# MonkeyParty7_1.net
KiCad netlist of a schematic drawn in EAGLE
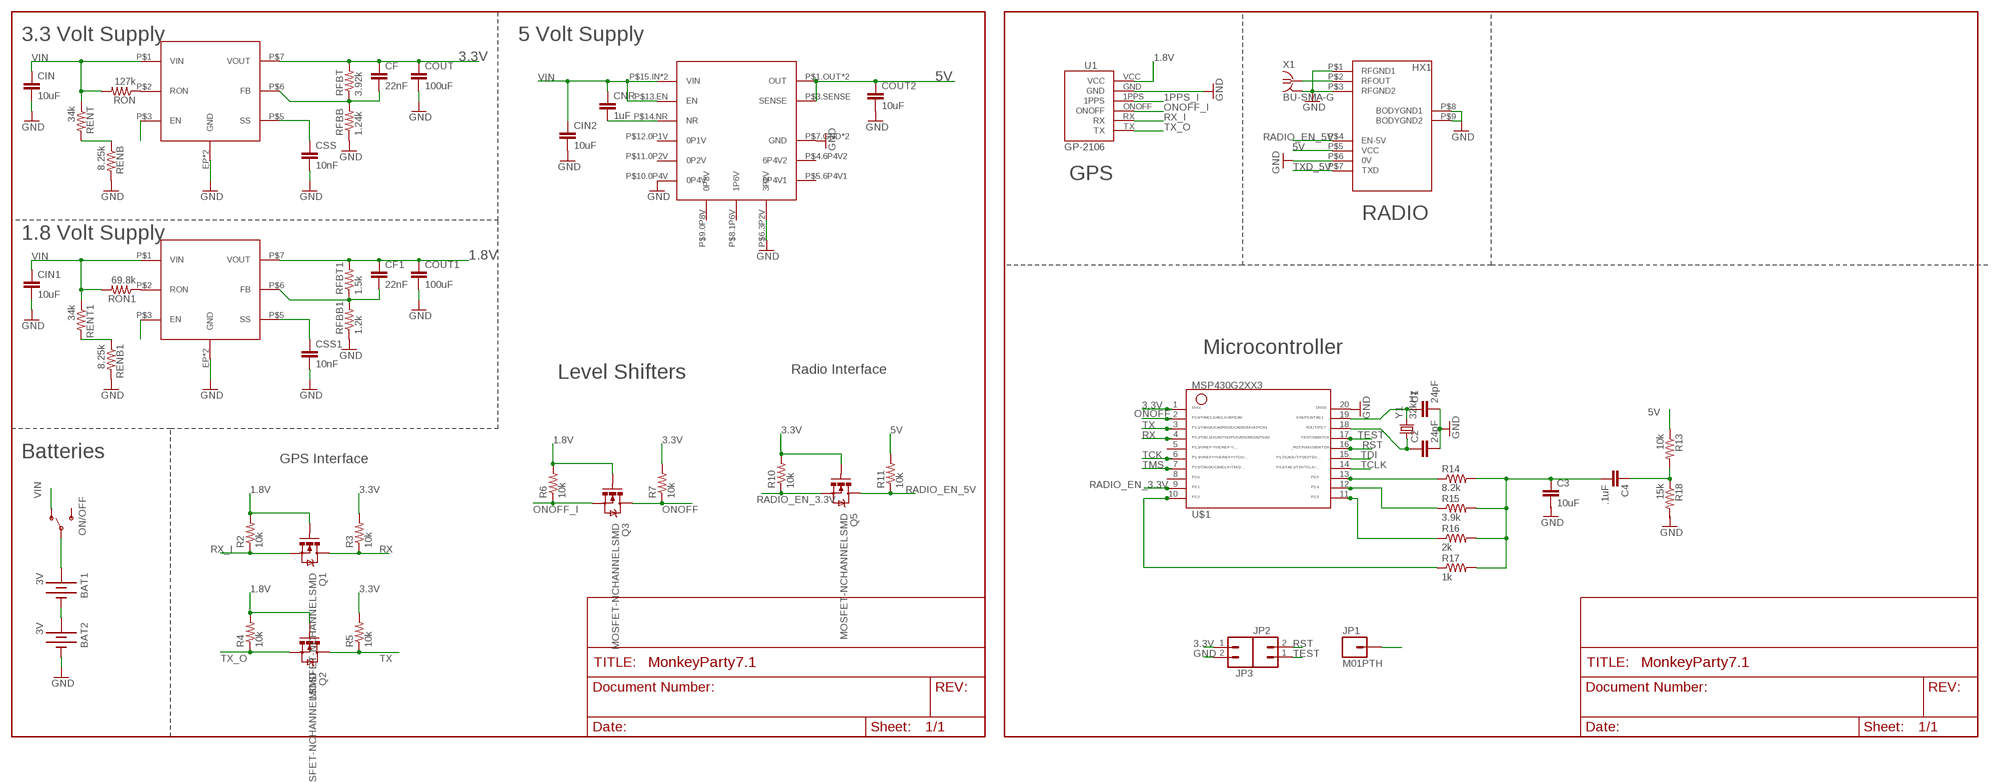
[diagram p0: schematic, sheet 1]

(export (version "E")
  (design (tool "Eeschema 10.0.6"))
  (components
    (comp (ref "1.8VREG")
      (value "LMZ12001")
      (footprint "eagle-import:TO-PMOD7PIN")
      (libsource (lib "eagle-import") (part "LMZ12001"))
    )
    (comp (ref "3.3VREG")
      (value "LMZ12001")
      (footprint "eagle-import:TO-PMOD7PIN")
      (libsource (lib "eagle-import") (part "LMZ12001"))
    )
    (comp (ref "5VREG")
      (value "TPS7A4700")
      (footprint "eagle-import:S-PVQFN-N20")
      (libsource (lib "eagle-import") (part "TPS7A4700"))
    )
    (comp (ref "BAT1")
      (value "3V")
      (footprint "eagle-import:BATTCON_245MM")
      (libsource (lib "eagle-import") (part "BATTERY245MM"))
    )
    (comp (ref "BAT2")
      (value "3V")
      (footprint "eagle-import:BATTCON_245MM")
      (libsource (lib "eagle-import") (part "BATTERY245MM"))
    )
    (comp (ref "C1")
      (value "24pF")
      (footprint "eagle-import:1210")
      (libsource (lib "eagle-import") (part "CAP1210"))
    )
    (comp (ref "C2")
      (value "24pF")
      (footprint "eagle-import:1210")
      (libsource (lib "eagle-import") (part "CAP1210"))
    )
    (comp (ref "C3")
      (value "10uF")
      (footprint "eagle-import:0805")
      (libsource (lib "eagle-import") (part "SparkFun-Capacitors_CAP0805"))
    )
    (comp (ref "C4")
      (value ".1uF")
      (footprint "eagle-import:0805")
      (libsource (lib "eagle-import") (part "SparkFun-Capacitors_CAP0805"))
    )
    (comp (ref "CF")
      (value "22nF")
      (footprint "eagle-import:0805")
      (libsource (lib "eagle-import") (part "CAP0805"))
    )
    (comp (ref "CF1")
      (value "22nF")
      (footprint "eagle-import:0805")
      (libsource (lib "eagle-import") (part "CAP0805"))
    )
    (comp (ref "CIN")
      (value "10uF")
      (footprint "eagle-import:0805")
      (libsource (lib "eagle-import") (part "CAP0805"))
    )
    (comp (ref "CIN1")
      (value "10uF")
      (footprint "eagle-import:0805")
      (libsource (lib "eagle-import") (part "CAP0805"))
    )
    (comp (ref "CIN2")
      (value "10uF")
      (footprint "eagle-import:0805")
      (libsource (lib "eagle-import") (part "CAP0805"))
    )
    (comp (ref "CNR")
      (value "1uF")
      (footprint "eagle-import:0805")
      (libsource (lib "eagle-import") (part "CAP0805"))
    )
    (comp (ref "COUT")
      (value "100uF")
      (footprint "eagle-import:1210")
      (libsource (lib "eagle-import") (part "CAP1210"))
    )
    (comp (ref "COUT1")
      (value "100uF")
      (footprint "eagle-import:1210")
      (libsource (lib "eagle-import") (part "CAP1210"))
    )
    (comp (ref "COUT2")
      (value "10uF")
      (footprint "eagle-import:0805")
      (libsource (lib "eagle-import") (part "CAP0805"))
    )
    (comp (ref "CSS")
      (value "10nF")
      (footprint "eagle-import:1210")
      (libsource (lib "eagle-import") (part "CAP1210"))
    )
    (comp (ref "CSS1")
      (value "10nF")
      (footprint "eagle-import:1210")
      (libsource (lib "eagle-import") (part "CAP1210"))
    )
    (comp (ref "JP1")
      (value "M01PTH")
      (footprint "eagle-import:1X01")
      (libsource (lib "eagle-import") (part "M01PTH"))
    )
    (comp (ref "JP2")
      (value "M02PTH")
      (footprint "eagle-import:1X02")
      (libsource (lib "eagle-import") (part "M02PTH"))
    )
    (comp (ref "JP3")
      (value "M02PTH")
      (footprint "eagle-import:1X02")
      (libsource (lib "eagle-import") (part "M02PTH"))
    )
    (comp (ref "ON/OFF")
      (value "SWITCH-SPSTKIT")
      (footprint "eagle-import:SWITCH-SPDT_KIT")
      (libsource (lib "eagle-import") (part "SWITCH-SPSTKIT"))
    )
    (comp (ref "Q1")
      (value "MOSFET-NCHANNELSMD")
      (footprint "eagle-import:SOT23-3")
      (libsource (lib "eagle-import") (part "MOSFET-NCHANNELSMD"))
    )
    (comp (ref "Q2")
      (value "MOSFET-NCHANNELSMD")
      (footprint "eagle-import:SOT23-3")
      (libsource (lib "eagle-import") (part "MOSFET-NCHANNELSMD"))
    )
    (comp (ref "Q3")
      (value "MOSFET-NCHANNELSMD")
      (footprint "eagle-import:SOT23-3")
      (libsource (lib "eagle-import") (part "MOSFET-NCHANNELSMD"))
    )
    (comp (ref "Q5")
      (value "MOSFET-NCHANNELSMD")
      (footprint "eagle-import:SOT23-3")
      (libsource (lib "eagle-import") (part "MOSFET-NCHANNELSMD"))
    )
    (comp (ref "R2")
      (value "10k")
      (footprint "eagle-import:0805")
      (libsource (lib "eagle-import") (part "RESISTOR0805-RES"))
    )
    (comp (ref "R3")
      (value "10k")
      (footprint "eagle-import:0805")
      (libsource (lib "eagle-import") (part "RESISTOR0805-RES"))
    )
    (comp (ref "R4")
      (value "10k")
      (footprint "eagle-import:0805")
      (libsource (lib "eagle-import") (part "RESISTOR0805-RES"))
    )
    (comp (ref "R5")
      (value "10k")
      (footprint "eagle-import:0805")
      (libsource (lib "eagle-import") (part "RESISTOR0805-RES"))
    )
    (comp (ref "R6")
      (value "10k")
      (footprint "eagle-import:0805")
      (libsource (lib "eagle-import") (part "RESISTOR0805-RES"))
    )
    (comp (ref "R7")
      (value "10k")
      (footprint "eagle-import:0805")
      (libsource (lib "eagle-import") (part "RESISTOR0805-RES"))
    )
    (comp (ref "R10")
      (value "10k")
      (footprint "eagle-import:0805")
      (libsource (lib "eagle-import") (part "RESISTOR0805-RES"))
    )
    (comp (ref "R11")
      (value "10k")
      (footprint "eagle-import:0805")
      (libsource (lib "eagle-import") (part "RESISTOR0805-RES"))
    )
    (comp (ref "R13")
      (value "10k")
      (footprint "eagle-import:0805")
      (libsource (lib "eagle-import") (part "SparkFun-Resistors_RESISTOR0805-RES"))
    )
    (comp (ref "R14")
      (value "8.2k")
      (footprint "eagle-import:0805")
      (libsource (lib "eagle-import") (part "RESISTOR0805-RES"))
    )
    (comp (ref "R15")
      (value "3.9k")
      (footprint "eagle-import:0805")
      (libsource (lib "eagle-import") (part "RESISTOR0805-RES"))
    )
    (comp (ref "R16")
      (value "2k")
      (footprint "eagle-import:0805")
      (libsource (lib "eagle-import") (part "RESISTOR0805-RES"))
    )
    (comp (ref "R17")
      (value "1k")
      (footprint "eagle-import:0805")
      (libsource (lib "eagle-import") (part "RESISTOR0805-RES"))
    )
    (comp (ref "R18")
      (value "15k")
      (footprint "eagle-import:0805")
      (libsource (lib "eagle-import") (part "SparkFun-Resistors_RESISTOR0805-RES"))
    )
    (comp (ref "RENB")
      (value "8.25k")
      (footprint "eagle-import:0805")
      (libsource (lib "eagle-import") (part "RESISTOR0805-RES"))
    )
    (comp (ref "RENB1")
      (value "8.25k")
      (footprint "eagle-import:0805")
      (libsource (lib "eagle-import") (part "RESISTOR0805-RES"))
    )
    (comp (ref "RENT")
      (value "34k")
      (footprint "eagle-import:0805")
      (libsource (lib "eagle-import") (part "RESISTOR0805-RES"))
    )
    (comp (ref "RENT1")
      (value "34k")
      (footprint "eagle-import:0805")
      (libsource (lib "eagle-import") (part "RESISTOR0805-RES"))
    )
    (comp (ref "RFBB")
      (value "1.24k")
      (footprint "eagle-import:0805")
      (libsource (lib "eagle-import") (part "RESISTOR0805-RES"))
    )
    (comp (ref "RFBB1")
      (value "1.2k")
      (footprint "eagle-import:0805")
      (libsource (lib "eagle-import") (part "RESISTOR0805-RES"))
    )
    (comp (ref "RFBT")
      (value "3.92k")
      (footprint "eagle-import:0805")
      (libsource (lib "eagle-import") (part "RESISTOR0805-RES"))
    )
    (comp (ref "RFBT1")
      (value "1.5k")
      (footprint "eagle-import:0805")
      (libsource (lib "eagle-import") (part "RESISTOR0805-RES"))
    )
    (comp (ref "RON")
      (value "127k")
      (footprint "eagle-import:0805")
      (libsource (lib "eagle-import") (part "RESISTOR0805-RES"))
    )
    (comp (ref "RON1")
      (value "69.8k")
      (footprint "eagle-import:0805")
      (libsource (lib "eagle-import") (part "RESISTOR0805-RES"))
    )
    (comp (ref "U$1")
      (value "G2XX3---PW20")
      (footprint "eagle-import:PW20")
      (libsource (lib "eagle-import") (part "G2XX3---PW20"))
    )
    (comp (ref "U$2")
      (value "HX1")
      (footprint "eagle-import:HX1")
      (libsource (lib "eagle-import") (part "HX1"))
    )
    (comp (ref "U1")
      (value "GP-2106")
      (footprint "eagle-import:GP-2106")
      (libsource (lib "eagle-import") (part "GP-2106"))
    )
    (comp (ref "X1")
      (value "BU-SMA-G")
      (footprint "eagle-import:BU-SMA-G")
      (libsource (lib "eagle-import") (part "BU-SMA-G"))
    )
    (comp (ref "Y1")
      (value "32kHz")
      (footprint "eagle-import:CRYSTAL-32KHZ-SMD")
      (libsource (lib "eagle-import") (part "CRYSTAL32-SMD"))
    )
  )
  (nets
    (net (code "1") (name "/1.8V") (class "Default")
      (node (ref "1.8VREG") (pin "P$7") (pinfunction "VOUT_P$7") (pintype "bidirectional"))
      (node (ref "CF1") (pin "1") (pinfunction "1_1") (pintype "passive"))
      (node (ref "COUT1") (pin "1") (pinfunction "1_1") (pintype "passive"))
      (node (ref "Q1") (pin "1") (pinfunction "G_1") (pintype "passive"))
      (node (ref "Q2") (pin "1") (pinfunction "G_1") (pintype "passive"))
      (node (ref "Q3") (pin "1") (pinfunction "G_1") (pintype "passive"))
      (node (ref "R2") (pin "2") (pinfunction "2_2") (pintype "passive"))
      (node (ref "R4") (pin "2") (pinfunction "2_2") (pintype "passive"))
      (node (ref "R6") (pin "2") (pinfunction "2_2") (pintype "passive"))
      (node (ref "RFBT1") (pin "2") (pinfunction "2_2") (pintype "passive"))
      (node (ref "U1") (pin "VCC") (pinfunction "VCC_VCC") (pintype "bidirectional"))
    )
    (net (code "2") (name "/1PPS_I") (class "Default")
      (node (ref "U1") (pin "1PPS") (pinfunction "1PPS_1PPS") (pintype "bidirectional"))
    )
    (net (code "3") (name "/3.3V") (class "Default")
      (node (ref "3.3VREG") (pin "P$7") (pinfunction "VOUT_P$7") (pintype "bidirectional"))
      (node (ref "CF") (pin "1") (pinfunction "1_1") (pintype "passive"))
      (node (ref "COUT") (pin "1") (pinfunction "1_1") (pintype "passive"))
      (node (ref "JP3") (pin "1") (pinfunction "1_1") (pintype "passive"))
      (node (ref "Q5") (pin "1") (pinfunction "G_1") (pintype "passive"))
      (node (ref "R10") (pin "2") (pinfunction "2_2") (pintype "passive"))
      (node (ref "R3") (pin "2") (pinfunction "2_2") (pintype "passive"))
      (node (ref "R5") (pin "2") (pinfunction "2_2") (pintype "passive"))
      (node (ref "R7") (pin "2") (pinfunction "2_2") (pintype "passive"))
      (node (ref "RFBT") (pin "2") (pinfunction "2_2") (pintype "passive"))
      (node (ref "U$1") (pin "1") (pinfunction "1_1") (pintype "bidirectional"))
    )
    (net (code "4") (name "/5V") (class "Default")
      (node (ref "5VREG") (pin "P$1.OUT") (pinfunction "OUT_P$1.OUT") (pintype "bidirectional"))
      (node (ref "5VREG") (pin "P$20.OUT") (pinfunction "OUT_P$20.OUT") (pintype "bidirectional"))
      (node (ref "5VREG") (pin "P$3.SENSE") (pinfunction "SENSE_P$3.SENSE") (pintype "bidirectional"))
      (node (ref "COUT2") (pin "1") (pinfunction "1_1") (pintype "passive"))
      (node (ref "R11") (pin "2") (pinfunction "2_2") (pintype "passive"))
      (node (ref "R13") (pin "1") (pinfunction "1_1") (pintype "passive"))
      (node (ref "U$2") (pin "P$5") (pinfunction "VCC_P$5") (pintype "bidirectional"))
    )
    (net (code "5") (name "/ONOFF") (class "Default")
      (node (ref "Q3") (pin "3") (pinfunction "D_3") (pintype "passive"))
      (node (ref "R7") (pin "1") (pinfunction "1_1") (pintype "passive"))
      (node (ref "U$1") (pin "2") (pinfunction "2_2") (pintype "bidirectional"))
    )
    (net (code "6") (name "/ONOFF_I") (class "Default")
      (node (ref "Q3") (pin "2") (pinfunction "S_2") (pintype "passive"))
      (node (ref "R6") (pin "1") (pinfunction "1_1") (pintype "passive"))
      (node (ref "U1") (pin "ONOFF") (pinfunction "ONOFF_ONOFF") (pintype "bidirectional"))
    )
    (net (code "7") (name "/RADIO_EN_3.3V") (class "Default")
      (node (ref "Q5") (pin "2") (pinfunction "S_2") (pintype "passive"))
      (node (ref "R10") (pin "1") (pinfunction "1_1") (pintype "passive"))
      (node (ref "U$1") (pin "9") (pinfunction "9_9") (pintype "bidirectional"))
    )
    (net (code "8") (name "/RADIO_EN_5V") (class "Default")
      (node (ref "Q5") (pin "3") (pinfunction "D_3") (pintype "passive"))
      (node (ref "R11") (pin "1") (pinfunction "1_1") (pintype "passive"))
      (node (ref "U$2") (pin "P$4") (pinfunction "EN-5V_P$4") (pintype "bidirectional"))
    )
    (net (code "9") (name "/RST") (class "Default")
      (node (ref "JP2") (pin "2") (pinfunction "2_2") (pintype "passive"))
      (node (ref "U$1") (pin "16") (pinfunction "16_16") (pintype "bidirectional"))
    )
    (net (code "10") (name "/RX") (class "Default")
      (node (ref "Q1") (pin "3") (pinfunction "D_3") (pintype "passive"))
      (node (ref "R3") (pin "1") (pinfunction "1_1") (pintype "passive"))
      (node (ref "U$1") (pin "4") (pinfunction "4_4") (pintype "bidirectional"))
    )
    (net (code "11") (name "/RX_I") (class "Default")
      (node (ref "Q1") (pin "2") (pinfunction "S_2") (pintype "passive"))
      (node (ref "R2") (pin "1") (pinfunction "1_1") (pintype "passive"))
      (node (ref "U1") (pin "RX") (pinfunction "RX_RX") (pintype "bidirectional"))
    )
    (net (code "12") (name "/TCK") (class "Default")
      (node (ref "U$1") (pin "6") (pinfunction "6_6") (pintype "bidirectional"))
    )
    (net (code "13") (name "/TCLK") (class "Default")
      (node (ref "U$1") (pin "14") (pinfunction "14_14") (pintype "bidirectional"))
    )
    (net (code "14") (name "/TDI") (class "Default")
      (node (ref "U$1") (pin "15") (pinfunction "15_15") (pintype "bidirectional"))
    )
    (net (code "15") (name "/TEST") (class "Default")
      (node (ref "JP2") (pin "1") (pinfunction "1_1") (pintype "passive"))
      (node (ref "U$1") (pin "17") (pinfunction "17_17") (pintype "bidirectional"))
    )
    (net (code "16") (name "/TMS") (class "Default")
      (node (ref "U$1") (pin "7") (pinfunction "7_7") (pintype "bidirectional"))
    )
    (net (code "17") (name "/TX") (class "Default")
      (node (ref "Q2") (pin "3") (pinfunction "D_3") (pintype "passive"))
      (node (ref "R5") (pin "1") (pinfunction "1_1") (pintype "passive"))
      (node (ref "U$1") (pin "3") (pinfunction "3_3") (pintype "bidirectional"))
    )
    (net (code "18") (name "/TXD_5V") (class "Default")
      (node (ref "C4") (pin "1") (pinfunction "1_1") (pintype "passive"))
      (node (ref "R13") (pin "2") (pinfunction "2_2") (pintype "passive"))
      (node (ref "R18") (pin "1") (pinfunction "1_1") (pintype "passive"))
      (node (ref "U$2") (pin "P$7") (pinfunction "TXD_P$7") (pintype "bidirectional"))
    )
    (net (code "19") (name "/TX_O") (class "Default")
      (node (ref "Q2") (pin "2") (pinfunction "S_2") (pintype "passive"))
      (node (ref "R4") (pin "1") (pinfunction "1_1") (pintype "passive"))
      (node (ref "U1") (pin "TX") (pinfunction "TX_TX") (pintype "bidirectional"))
    )
    (net (code "20") (name "/VIN") (class "Default")
      (node (ref "1.8VREG") (pin "P$1") (pinfunction "VIN_P$1") (pintype "bidirectional"))
      (node (ref "1.8VREG") (pin "P$3") (pinfunction "EN_P$3") (pintype "bidirectional"))
      (node (ref "3.3VREG") (pin "P$1") (pinfunction "VIN_P$1") (pintype "bidirectional"))
      (node (ref "3.3VREG") (pin "P$3") (pinfunction "EN_P$3") (pintype "bidirectional"))
      (node (ref "5VREG") (pin "P$13.EN") (pinfunction "EN_P$13.EN") (pintype "bidirectional"))
      (node (ref "5VREG") (pin "P$15.IN") (pinfunction "VIN_P$15.IN") (pintype "bidirectional"))
      (node (ref "5VREG") (pin "P$16.IN") (pinfunction "VIN_P$16.IN") (pintype "bidirectional"))
      (node (ref "CIN") (pin "1") (pinfunction "1_1") (pintype "passive"))
      (node (ref "CIN1") (pin "1") (pinfunction "1_1") (pintype "passive"))
      (node (ref "CIN2") (pin "1") (pinfunction "1_1") (pintype "passive"))
      (node (ref "CNR") (pin "1") (pinfunction "1_1") (pintype "passive"))
      (node (ref "JP1") (pin "1") (pinfunction "1_1") (pintype "passive"))
      (node (ref "ON/OFF") (pin "1") (pinfunction "O_1") (pintype "passive"))
      (node (ref "RENT") (pin "1") (pinfunction "1_1") (pintype "passive"))
      (node (ref "RENT1") (pin "1") (pinfunction "1_1") (pintype "passive"))
      (node (ref "RON") (pin "2") (pinfunction "2_2") (pintype "passive"))
      (node (ref "RON1") (pin "2") (pinfunction "2_2") (pintype "passive"))
    )
    (net (code "21") (name "GND") (class "Default")
      (node (ref "1.8VREG") (pin "EP") (pinfunction "GND_EP") (pintype "bidirectional"))
      (node (ref "1.8VREG") (pin "P$4") (pinfunction "GND_P$4") (pintype "bidirectional"))
      (node (ref "3.3VREG") (pin "EP") (pinfunction "GND_EP") (pintype "bidirectional"))
      (node (ref "3.3VREG") (pin "P$4") (pinfunction "GND_P$4") (pintype "bidirectional"))
      (node (ref "5VREG") (pin "P$10.0P4V") (pinfunction "0P4V_P$10.0P4V") (pintype "bidirectional"))
      (node (ref "5VREG") (pin "P$21.GND") (pinfunction "GND_P$21.GND") (pintype "bidirectional"))
      (node (ref "5VREG") (pin "P$6.3P2V") (pinfunction "3P2V_P$6.3P2V") (pintype "bidirectional"))
      (node (ref "5VREG") (pin "P$7.GND") (pinfunction "GND_P$7.GND") (pintype "bidirectional"))
      (node (ref "BAT2") (pin "2") (pinfunction "-_2") (pintype "power_in"))
      (node (ref "C1") (pin "2") (pinfunction "2_2") (pintype "passive"))
      (node (ref "C2") (pin "2") (pinfunction "2_2") (pintype "passive"))
      (node (ref "CIN") (pin "2") (pinfunction "2_2") (pintype "passive"))
      (node (ref "CIN1") (pin "2") (pinfunction "2_2") (pintype "passive"))
      (node (ref "CIN2") (pin "2") (pinfunction "2_2") (pintype "passive"))
      (node (ref "COUT") (pin "2") (pinfunction "2_2") (pintype "passive"))
      (node (ref "COUT1") (pin "2") (pinfunction "2_2") (pintype "passive"))
      (node (ref "COUT2") (pin "2") (pinfunction "2_2") (pintype "passive"))
      (node (ref "CSS") (pin "2") (pinfunction "2_2") (pintype "passive"))
      (node (ref "CSS1") (pin "2") (pinfunction "2_2") (pintype "passive"))
      (node (ref "JP3") (pin "2") (pinfunction "2_2") (pintype "passive"))
      (node (ref "RENB") (pin "2") (pinfunction "2_2") (pintype "passive"))
      (node (ref "RENB1") (pin "2") (pinfunction "2_2") (pintype "passive"))
      (node (ref "RFBB") (pin "1") (pinfunction "1_1") (pintype "passive"))
      (node (ref "RFBB1") (pin "1") (pinfunction "1_1") (pintype "passive"))
      (node (ref "U$1") (pin "20") (pinfunction "20_20") (pintype "bidirectional"))
      (node (ref "U$2") (pin "P$1") (pinfunction "RFGND1_P$1") (pintype "bidirectional"))
      (node (ref "U$2") (pin "P$3") (pinfunction "RFGND2_P$3") (pintype "bidirectional"))
      (node (ref "U$2") (pin "P$6") (pinfunction "0V_P$6") (pintype "bidirectional"))
      (node (ref "U$2") (pin "P$8") (pinfunction "BODYGND1_P$8") (pintype "bidirectional"))
      (node (ref "U$2") (pin "P$9") (pinfunction "BODYGND2_P$9") (pintype "bidirectional"))
      (node (ref "U1") (pin "GND") (pinfunction "GND_GND") (pintype "bidirectional"))
      (node (ref "X1") (pin "2") (pinfunction "2_2") (pintype "passive"))
      (node (ref "X1") (pin "3") (pinfunction "2_3") (pintype "passive"))
      (node (ref "X1") (pin "4") (pinfunction "2_4") (pintype "passive"))
      (node (ref "X1") (pin "5") (pinfunction "2_5") (pintype "passive"))
    )
    (net (code "22") (name "Net-(1.8VREG-FB)") (class "Default")
      (node (ref "1.8VREG") (pin "P$6") (pinfunction "FB_P$6") (pintype "bidirectional"))
      (node (ref "CF1") (pin "2") (pinfunction "2_2") (pintype "passive"))
      (node (ref "RFBB1") (pin "2") (pinfunction "2_2") (pintype "passive"))
      (node (ref "RFBT1") (pin "1") (pinfunction "1_1") (pintype "passive"))
    )
    (net (code "23") (name "Net-(1.8VREG-RON)") (class "Default")
      (node (ref "1.8VREG") (pin "P$2") (pinfunction "RON_P$2") (pintype "bidirectional"))
      (node (ref "RON1") (pin "1") (pinfunction "1_1") (pintype "passive"))
    )
    (net (code "24") (name "Net-(1.8VREG-SS)") (class "Default")
      (node (ref "1.8VREG") (pin "P$5") (pinfunction "SS_P$5") (pintype "bidirectional"))
      (node (ref "CSS1") (pin "1") (pinfunction "1_1") (pintype "passive"))
    )
    (net (code "25") (name "Net-(3.3VREG-FB)") (class "Default")
      (node (ref "3.3VREG") (pin "P$6") (pinfunction "FB_P$6") (pintype "bidirectional"))
      (node (ref "CF") (pin "2") (pinfunction "2_2") (pintype "passive"))
      (node (ref "RFBB") (pin "2") (pinfunction "2_2") (pintype "passive"))
      (node (ref "RFBT") (pin "1") (pinfunction "1_1") (pintype "passive"))
    )
    (net (code "26") (name "Net-(3.3VREG-RON)") (class "Default")
      (node (ref "3.3VREG") (pin "P$2") (pinfunction "RON_P$2") (pintype "bidirectional"))
      (node (ref "RON") (pin "1") (pinfunction "1_1") (pintype "passive"))
    )
    (net (code "27") (name "Net-(3.3VREG-SS)") (class "Default")
      (node (ref "3.3VREG") (pin "P$5") (pinfunction "SS_P$5") (pintype "bidirectional"))
      (node (ref "CSS") (pin "1") (pinfunction "1_1") (pintype "passive"))
    )
    (net (code "28") (name "Net-(5VREG-NR)") (class "Default")
      (node (ref "5VREG") (pin "P$14.NR") (pinfunction "NR_P$14.NR") (pintype "bidirectional"))
      (node (ref "CNR") (pin "2") (pinfunction "2_2") (pintype "passive"))
    )
    (net (code "29") (name "Net-(BAT1-+)") (class "Default")
      (node (ref "BAT1") (pin "1") (pinfunction "+_1") (pintype "power_in"))
      (node (ref "ON/OFF") (pin "2") (pinfunction "P_2") (pintype "passive"))
    )
    (net (code "30") (name "Net-(BAT1--)") (class "Default")
      (node (ref "BAT1") (pin "2") (pinfunction "-_2") (pintype "power_in"))
      (node (ref "BAT2") (pin "1") (pinfunction "+_1") (pintype "power_in"))
    )
    (net (code "31") (name "Net-(C3-Pad1)") (class "Default")
      (node (ref "C3") (pin "1") (pinfunction "1_1") (pintype "passive"))
      (node (ref "C4") (pin "2") (pinfunction "2_2") (pintype "passive"))
      (node (ref "R14") (pin "2") (pinfunction "2_2") (pintype "passive"))
      (node (ref "R15") (pin "2") (pinfunction "2_2") (pintype "passive"))
      (node (ref "R16") (pin "2") (pinfunction "2_2") (pintype "passive"))
      (node (ref "R17") (pin "2") (pinfunction "2_2") (pintype "passive"))
    )
    (net (code "32") (name "Net-(R14-Pad1)") (class "Default")
      (node (ref "R14") (pin "1") (pinfunction "1_1") (pintype "passive"))
      (node (ref "U$1") (pin "13") (pinfunction "13_13") (pintype "bidirectional"))
    )
    (net (code "33") (name "Net-(R15-Pad1)") (class "Default")
      (node (ref "R15") (pin "1") (pinfunction "1_1") (pintype "passive"))
      (node (ref "U$1") (pin "12") (pinfunction "12_12") (pintype "bidirectional"))
    )
    (net (code "34") (name "Net-(R16-Pad1)") (class "Default")
      (node (ref "R16") (pin "1") (pinfunction "1_1") (pintype "passive"))
      (node (ref "U$1") (pin "11") (pinfunction "11_11") (pintype "bidirectional"))
    )
    (net (code "35") (name "Net-(R17-Pad1)") (class "Default")
      (node (ref "R17") (pin "1") (pinfunction "1_1") (pintype "passive"))
      (node (ref "U$1") (pin "10") (pinfunction "10_10") (pintype "bidirectional"))
    )
    (net (code "36") (name "Net-(RENB-Pad1)") (class "Default")
      (node (ref "RENB") (pin "1") (pinfunction "1_1") (pintype "passive"))
      (node (ref "RENT") (pin "2") (pinfunction "2_2") (pintype "passive"))
    )
    (net (code "37") (name "Net-(RENB1-Pad1)") (class "Default")
      (node (ref "RENB1") (pin "1") (pinfunction "1_1") (pintype "passive"))
      (node (ref "RENT1") (pin "2") (pinfunction "2_2") (pintype "passive"))
    )
    (net (code "38") (name "Net-(U$2-RFOUT)") (class "Default")
      (node (ref "U$2") (pin "P$2") (pinfunction "RFOUT_P$2") (pintype "bidirectional"))
      (node (ref "X1") (pin "1") (pinfunction "1_1") (pintype "passive"))
    )
    (net (code "39") (name "Net-(Y1-1)") (class "Default")
      (node (ref "C2") (pin "1") (pinfunction "1_1") (pintype "passive"))
      (node (ref "U$1") (pin "18") (pinfunction "18_18") (pintype "bidirectional"))
      (node (ref "Y1") (pin "X1") (pinfunction "1_X1") (pintype "passive"))
    )
    (net (code "40") (name "Net-(Y1-2)") (class "Default")
      (node (ref "C1") (pin "1") (pinfunction "1_1") (pintype "passive"))
      (node (ref "U$1") (pin "19") (pinfunction "19_19") (pintype "bidirectional"))
      (node (ref "Y1") (pin "X2") (pinfunction "2_X2") (pintype "passive"))
    )
    (net (code "41") (name "unconnected-(5VREG-0P1V-PadP$12.0P1V)") (class "Default")
      (node (ref "5VREG") (pin "P$12.0P1V") (pinfunction "0P1V_P$12.0P1V") (pintype "bidirectional"))
    )
    (net (code "42") (name "unconnected-(5VREG-0P2V-PadP$11.0P2V)") (class "Default")
      (node (ref "5VREG") (pin "P$11.0P2V") (pinfunction "0P2V_P$11.0P2V") (pintype "bidirectional"))
    )
    (net (code "43") (name "unconnected-(5VREG-0P8V-PadP$9.0P8V)") (class "Default")
      (node (ref "5VREG") (pin "P$9.0P8V") (pinfunction "0P8V_P$9.0P8V") (pintype "bidirectional"))
    )
    (net (code "44") (name "unconnected-(5VREG-1P6V-PadP$8.1P6V)") (class "Default")
      (node (ref "5VREG") (pin "P$8.1P6V") (pinfunction "1P6V_P$8.1P6V") (pintype "bidirectional"))
    )
    (net (code "45") (name "unconnected-(5VREG-6P4V1-PadP$5.6P4V1)") (class "Default")
      (node (ref "5VREG") (pin "P$5.6P4V1") (pinfunction "6P4V1_P$5.6P4V1") (pintype "bidirectional"))
    )
    (net (code "46") (name "unconnected-(5VREG-6P4V2-PadP$4.6P4V2)") (class "Default")
      (node (ref "5VREG") (pin "P$4.6P4V2") (pinfunction "6P4V2_P$4.6P4V2") (pintype "bidirectional"))
    )
    (net (code "47") (name "unconnected-(C3-Pad2)") (class "Default")
      (node (ref "C3") (pin "2") (pinfunction "2_2") (pintype "passive"))
    )
    (net (code "48") (name "unconnected-(ON/OFF-S-Pad3)") (class "Default")
      (node (ref "ON/OFF") (pin "3") (pinfunction "S_3") (pintype "passive"))
    )
    (net (code "49") (name "unconnected-(R18-Pad2)") (class "Default")
      (node (ref "R18") (pin "2") (pinfunction "2_2") (pintype "passive"))
    )
    (net (code "50") (name "unconnected-(U$1-Pad5)") (class "Default")
      (node (ref "U$1") (pin "5") (pinfunction "5_5") (pintype "bidirectional"))
    )
    (net (code "51") (name "unconnected-(U$1-Pad8)") (class "Default")
      (node (ref "U$1") (pin "8") (pinfunction "8_8") (pintype "bidirectional"))
    )
  )
)
